# Servos.net
KiCad netlist of a schematic drawn in Altium Designer
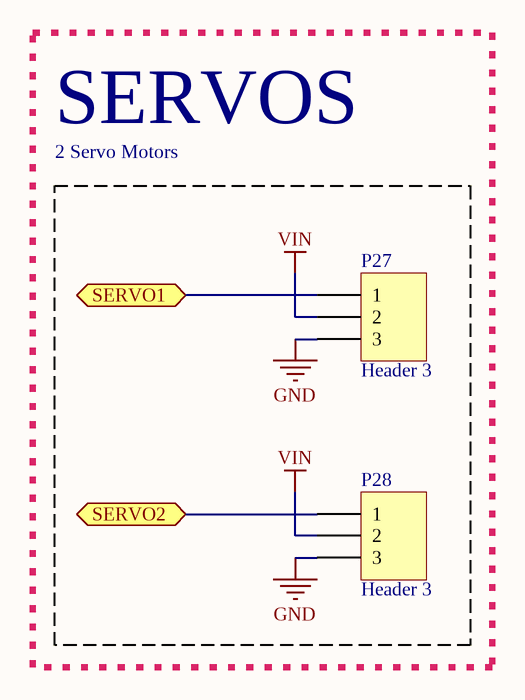
[diagram p0: Servos.SchDoc]

(export (version "E")
  (design (tool "Eeschema 10.0.6"))
  (components
    (comp (ref "P27")
      (value "Header 3")
      (footprint "HDR1X3")
      (description "Header, 3-Pin")
      (fields (field (name "PUBLISHER") "Altium Limited"))
      (libsource (lib "Miscellaneous Connectors") (part "Header 3"))
    )
    (comp (ref "P28")
      (value "Header 3")
      (footprint "HDR1X3")
      (description "Header, 3-Pin")
      (fields (field (name "PUBLISHER") "Altium Limited"))
      (libsource (lib "Miscellaneous Connectors") (part "Header 3"))
    )
  )
  (nets
    (net (code "1") (name "/SERVO1") (class "Default")
      (node (ref "P27") (pin "1") (pinfunction "1_1") (pintype "passive"))
    )
    (net (code "2") (name "/SERVO2") (class "Default")
      (node (ref "P28") (pin "1") (pinfunction "1_1") (pintype "passive"))
    )
    (net (code "3") (name "GND") (class "Default")
      (node (ref "P27") (pin "3") (pinfunction "3_3") (pintype "passive"))
      (node (ref "P28") (pin "3") (pinfunction "3_3") (pintype "passive"))
    )
    (net (code "4") (name "VIN") (class "Default")
      (node (ref "P27") (pin "2") (pinfunction "2_2") (pintype "passive"))
      (node (ref "P28") (pin "2") (pinfunction "2_2") (pintype "passive"))
    )
  )
)
